# senseStack_MainModule_schematic.net
KiCad netlist of a schematic drawn in EasyEDA
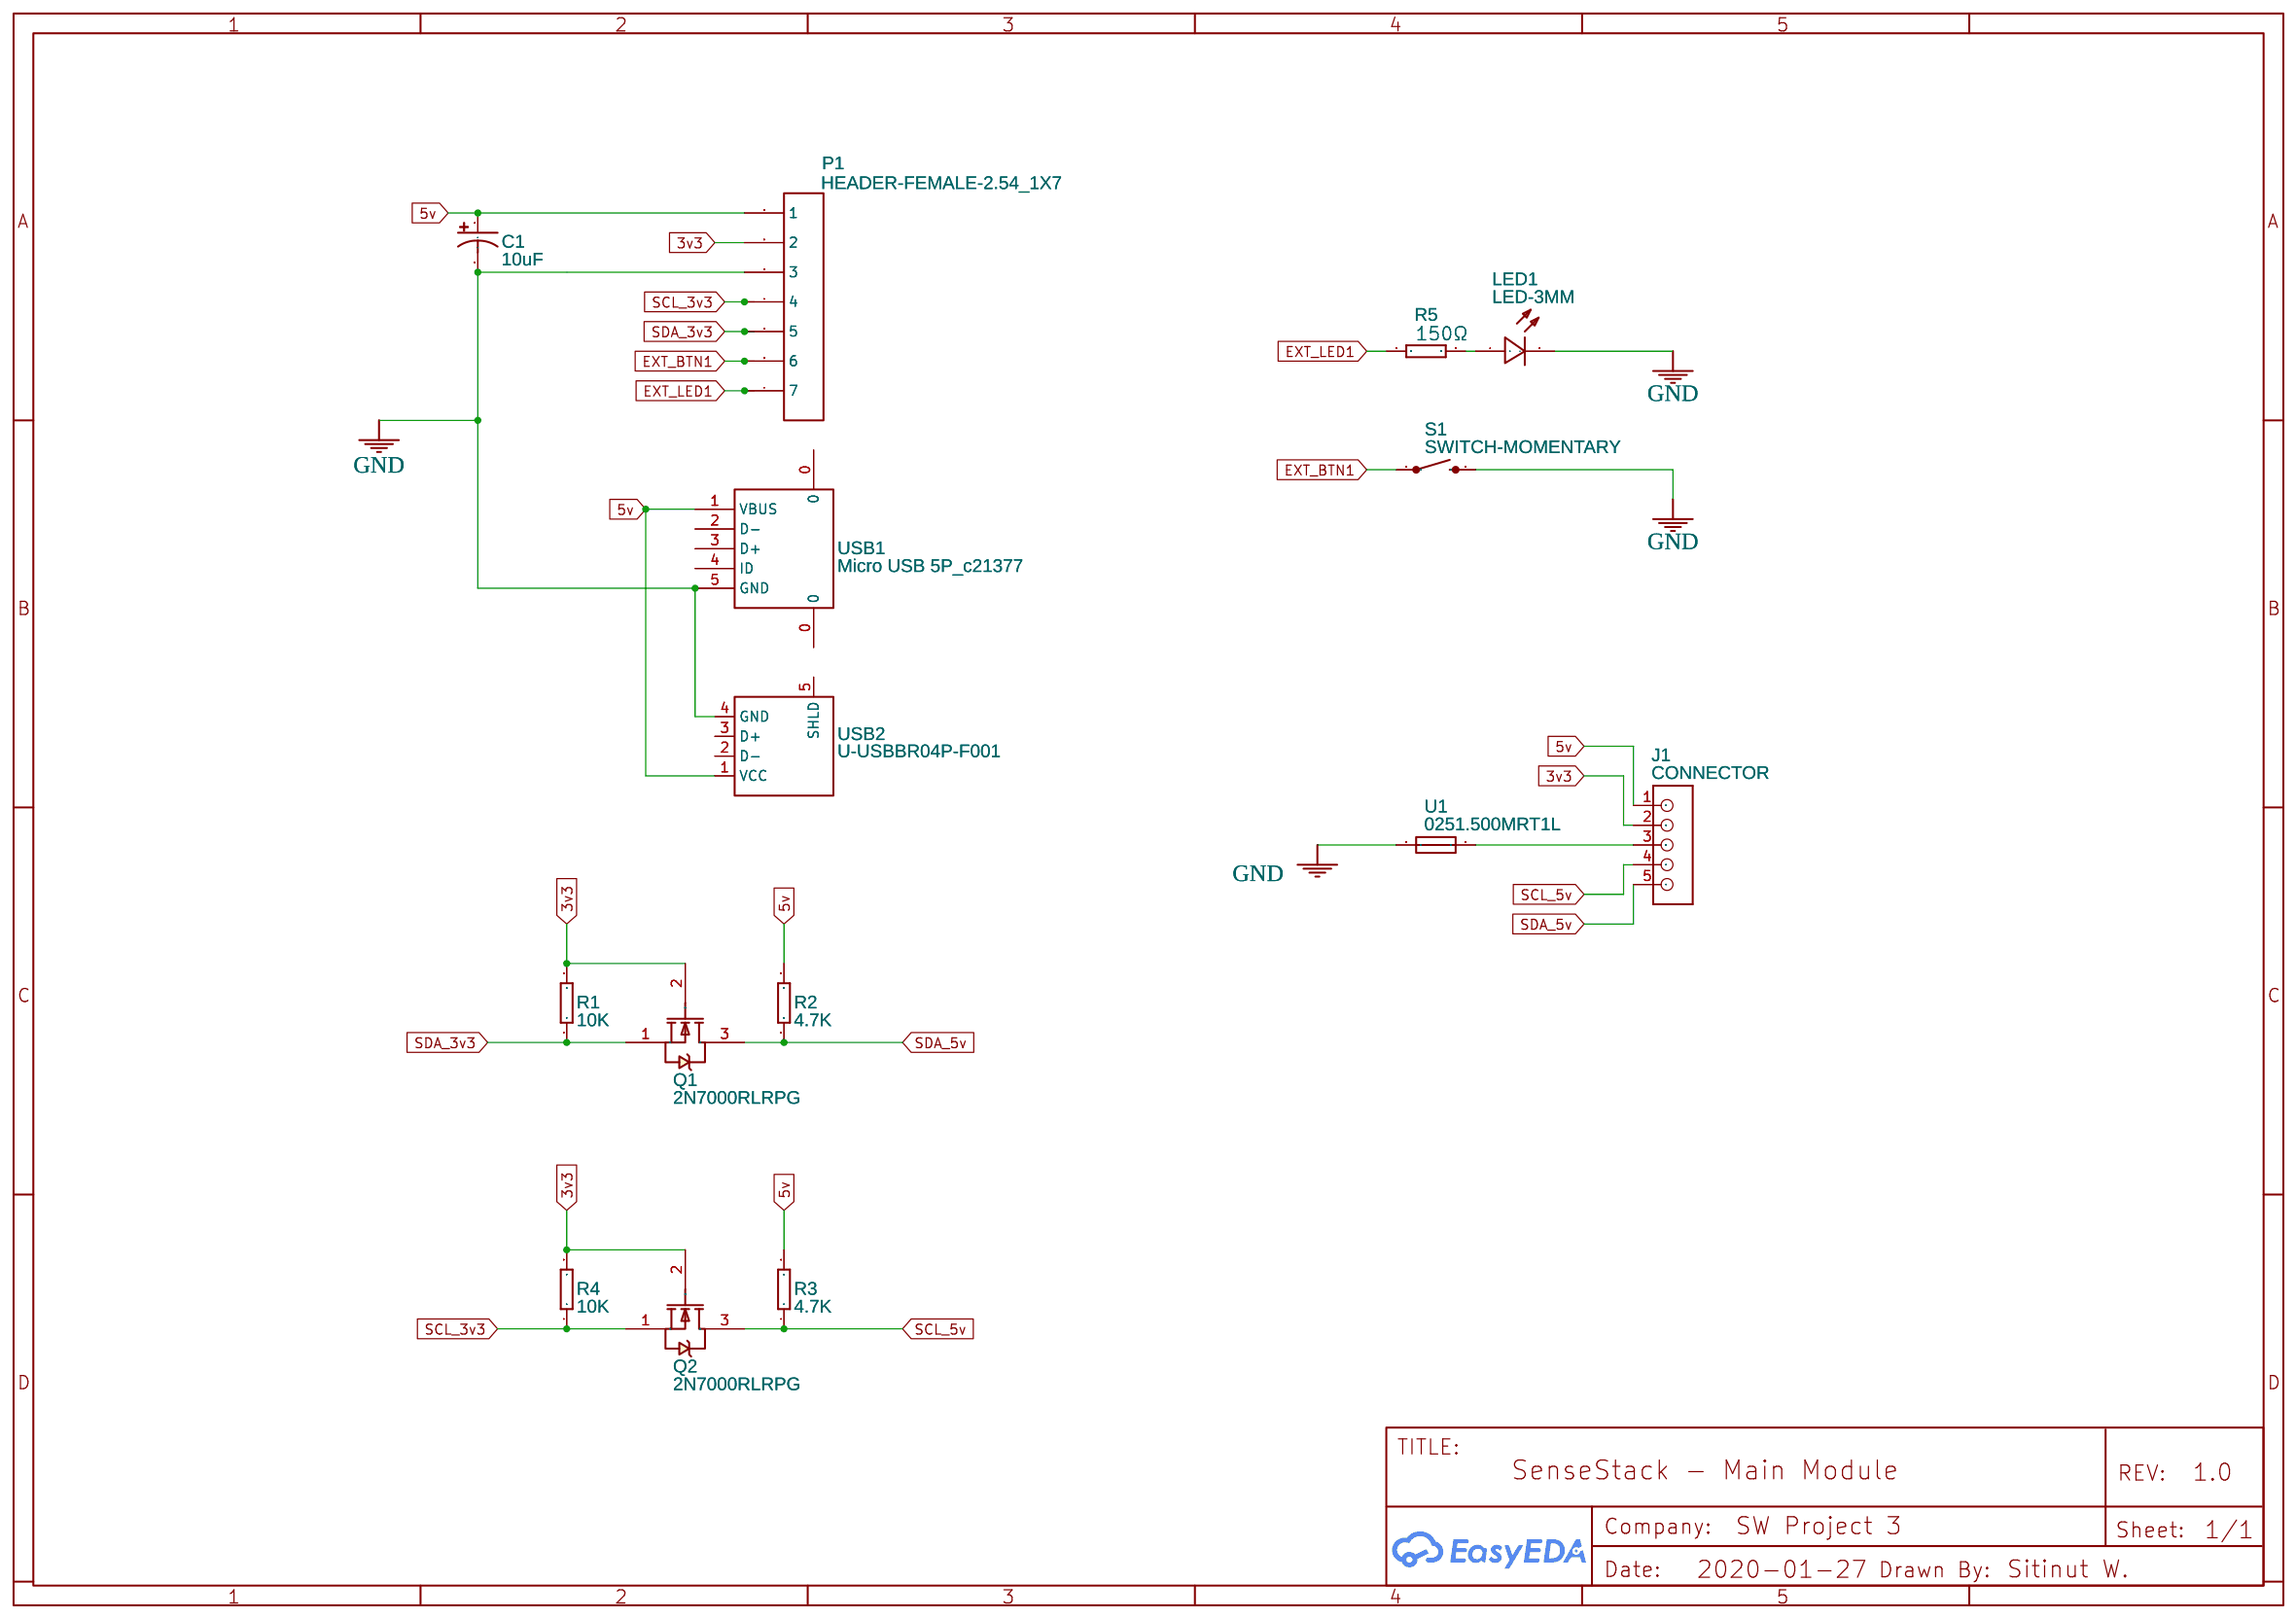
[diagram p0: schematic sheet]

(export (version "E")
  (design (tool "Eeschema 10.0.6"))
  (components
    (comp (ref "C1") (value "10uF") (libsource (lib "") (part "10UF-25V-20%(PTH)KIT")))
    (comp (ref "J1")
      (value "CONNECTOR")
      (libsource (lib "") (part "CONNECTOR_HEADER-6P_CONNECTOR_6P-2.54-8040MIL"))
    )
    (comp (ref "LED1")
      (value "LED-3MM")
      (fields
        (field (name "BOM_Manufacturer Part") "204-10SURD/S530-A3")
        (field (name "BOM_Supplier Part") "C99772")
      )
      (libsource (lib "") (part "LED-3MM"))
    )
    (comp (ref "P1")
      (value "HEADER-FEMALE-2.54_1X7")
      (fields
        (field (name "BOM_Manufacturer Part") "Header-Female-2.54_1x10")
        (field (name "BOM_Supplier Part") "undefined")
      )
      (libsource (lib "") (part "HEADER-FEMALE-2.54_1X7"))
    )
    (comp (ref "Q1") (value "2N7000RLRPG") (libsource (lib "") (part "2N7000RLRPG")))
    (comp (ref "Q2") (value "2N7000RLRPG") (libsource (lib "") (part "2N7000RLRPG")))
    (comp (ref "R1") (value "10K") (libsource (lib "") (part "RESISTOR")))
    (comp (ref "R2") (value "4.7K") (libsource (lib "") (part "RESISTOR")))
    (comp (ref "R3") (value "4.7K") (libsource (lib "") (part "RESISTOR")))
    (comp (ref "R4") (value "10K") (libsource (lib "") (part "RESISTOR")))
    (comp (ref "R5") (value "150Ω") (libsource (lib "") (part "RESISTOR_1")))
    (comp (ref "S1") (value "SWITCH-MOMENTARY") (libsource (lib "") (part "SWITCH-MOMENTARY-2SIDE_EZ")))
    (comp (ref "U1")
      (value "0251.500MRT1L")
      (fields (field (name "BOM_Supplier Part") "C142873"))
      (libsource (lib "") (part "0251.500MRT1L"))
    )
    (comp (ref "USB1")
      (value "Micro USB 5P_c21377")
      (fields (field (name "BOM_Supplier Part") "C21377"))
      (libsource (lib "") (part "Micro USB 5P_c21377"))
    )
    (comp (ref "USB2")
      (value "U-USBBR04P-F001")
      (fields (field (name "BOM_Supplier Part") "C386743"))
      (libsource (lib "") (part "U-USBBR04P-F001"))
    )
  )
  (nets
    (net (code "1") (name "3v3") (class "Default")
      (node (ref "J1") (pin "2") (pinfunction "2_2") (pintype "unspecified"))
      (node (ref "P1") (pin "2") (pinfunction "2_2") (pintype "input"))
      (node (ref "Q1") (pin "2") (pinfunction "G_2") (pintype "unspecified"))
      (node (ref "Q2") (pin "2") (pinfunction "G_2") (pintype "unspecified"))
      (node (ref "R1") (pin "2") (pinfunction "2_2") (pintype "unspecified"))
      (node (ref "R4") (pin "2") (pinfunction "2_2") (pintype "unspecified"))
    )
    (net (code "2") (name "5v") (class "Default")
      (node (ref "C1") (pin "1") (pinfunction "+_1") (pintype "unspecified"))
      (node (ref "J1") (pin "1") (pinfunction "1_1") (pintype "unspecified"))
      (node (ref "P1") (pin "1") (pinfunction "1_1") (pintype "input"))
      (node (ref "R2") (pin "2") (pinfunction "2_2") (pintype "unspecified"))
      (node (ref "R3") (pin "2") (pinfunction "2_2") (pintype "unspecified"))
      (node (ref "USB1") (pin "1") (pinfunction "VBUS_1") (pintype "unspecified"))
      (node (ref "USB2") (pin "1") (pinfunction "VCC_1") (pintype "input"))
    )
    (net (code "3") (name "EXT_BTN1") (class "Default")
      (node (ref "P1") (pin "6") (pinfunction "6_6") (pintype "input"))
      (node (ref "S1") (pin "1") (pinfunction "1_1") (pintype "unspecified"))
    )
    (net (code "4") (name "EXT_LED1") (class "Default")
      (node (ref "P1") (pin "7") (pinfunction "7_7") (pintype "input"))
      (node (ref "R5") (pin "1") (pinfunction "1_1") (pintype "unspecified"))
    )
    (net (code "5") (name "GND") (class "Default")
      (node (ref "C1") (pin "2") (pinfunction "-_2") (pintype "unspecified"))
      (node (ref "LED1") (pin "2") (pinfunction "-_2") (pintype "unspecified"))
      (node (ref "P1") (pin "3") (pinfunction "3_3") (pintype "input"))
      (node (ref "S1") (pin "2") (pinfunction "2_2") (pintype "unspecified"))
      (node (ref "U1") (pin "1") (pinfunction "1_1") (pintype "unspecified"))
      (node (ref "USB1") (pin "5") (pinfunction "GND_5") (pintype "unspecified"))
      (node (ref "USB2") (pin "4") (pinfunction "GND_4") (pintype "input"))
    )
    (net (code "6") (name "Net-(J1-Pad3)") (class "Default")
      (node (ref "J1") (pin "3") (pinfunction "3_3") (pintype "unspecified"))
      (node (ref "U1") (pin "2") (pinfunction "2_2") (pintype "unspecified"))
    )
    (net (code "7") (name "Net-(LED1-+)") (class "Default")
      (node (ref "LED1") (pin "1") (pinfunction "+_1") (pintype "unspecified"))
      (node (ref "R5") (pin "2") (pinfunction "2_2") (pintype "unspecified"))
    )
    (net (code "8") (name "SCL_3v3") (class "Default")
      (node (ref "P1") (pin "4") (pinfunction "4_4") (pintype "input"))
      (node (ref "Q2") (pin "1") (pinfunction "S_1") (pintype "unspecified"))
      (node (ref "R4") (pin "1") (pinfunction "1_1") (pintype "unspecified"))
    )
    (net (code "9") (name "SCL_5v") (class "Default")
      (node (ref "J1") (pin "4") (pinfunction "4_4") (pintype "unspecified"))
      (node (ref "Q2") (pin "3") (pinfunction "D_3") (pintype "unspecified"))
      (node (ref "R3") (pin "1") (pinfunction "1_1") (pintype "unspecified"))
    )
    (net (code "10") (name "SDA_3v3") (class "Default")
      (node (ref "P1") (pin "5") (pinfunction "5_5") (pintype "input"))
      (node (ref "Q1") (pin "1") (pinfunction "S_1") (pintype "unspecified"))
      (node (ref "R1") (pin "1") (pinfunction "1_1") (pintype "unspecified"))
    )
    (net (code "11") (name "SDA_5v") (class "Default")
      (node (ref "J1") (pin "5") (pinfunction "4_5") (pintype "unspecified"))
      (node (ref "Q1") (pin "3") (pinfunction "D_3") (pintype "unspecified"))
      (node (ref "R2") (pin "1") (pinfunction "1_1") (pintype "unspecified"))
    )
    (net (code "12") (name "unconnected-(USB1-D+-Pad3)") (class "Default")
      (node (ref "USB1") (pin "3") (pinfunction "D+_3") (pintype "unspecified"))
    )
    (net (code "13") (name "unconnected-(USB1-D--Pad2)") (class "Default")
      (node (ref "USB1") (pin "2") (pinfunction "D-_2") (pintype "unspecified"))
    )
    (net (code "14") (name "unconnected-(USB1-ID-Pad4)") (class "Default")
      (node (ref "USB1") (pin "4") (pinfunction "ID_4") (pintype "unspecified"))
    )
    (net (code "15") (name "unconnected-(USB1-Pad0)") (class "Default")
      (node (ref "USB1") (pin "0") (pinfunction "0_0") (pintype "unspecified"))
    )
    (net (code "16") (name "unconnected-(USB1-Pad0)_1") (class "Default")
      (node (ref "USB1") (pin "0") (pinfunction "0_0") (pintype "unspecified"))
    )
    (net (code "17") (name "unconnected-(USB2-D+-Pad3)") (class "Default")
      (node (ref "USB2") (pin "3") (pinfunction "D+_3") (pintype "input"))
    )
    (net (code "18") (name "unconnected-(USB2-D--Pad2)") (class "Default")
      (node (ref "USB2") (pin "2") (pinfunction "D-_2") (pintype "input"))
    )
    (net (code "19") (name "unconnected-(USB2-SHLD-Pad5)") (class "Default")
      (node (ref "USB2") (pin "5") (pinfunction "SHLD_5") (pintype "unspecified"))
    )
  )
)
